# clocktal.net
KiCad netlist of a schematic drawn in EAGLE
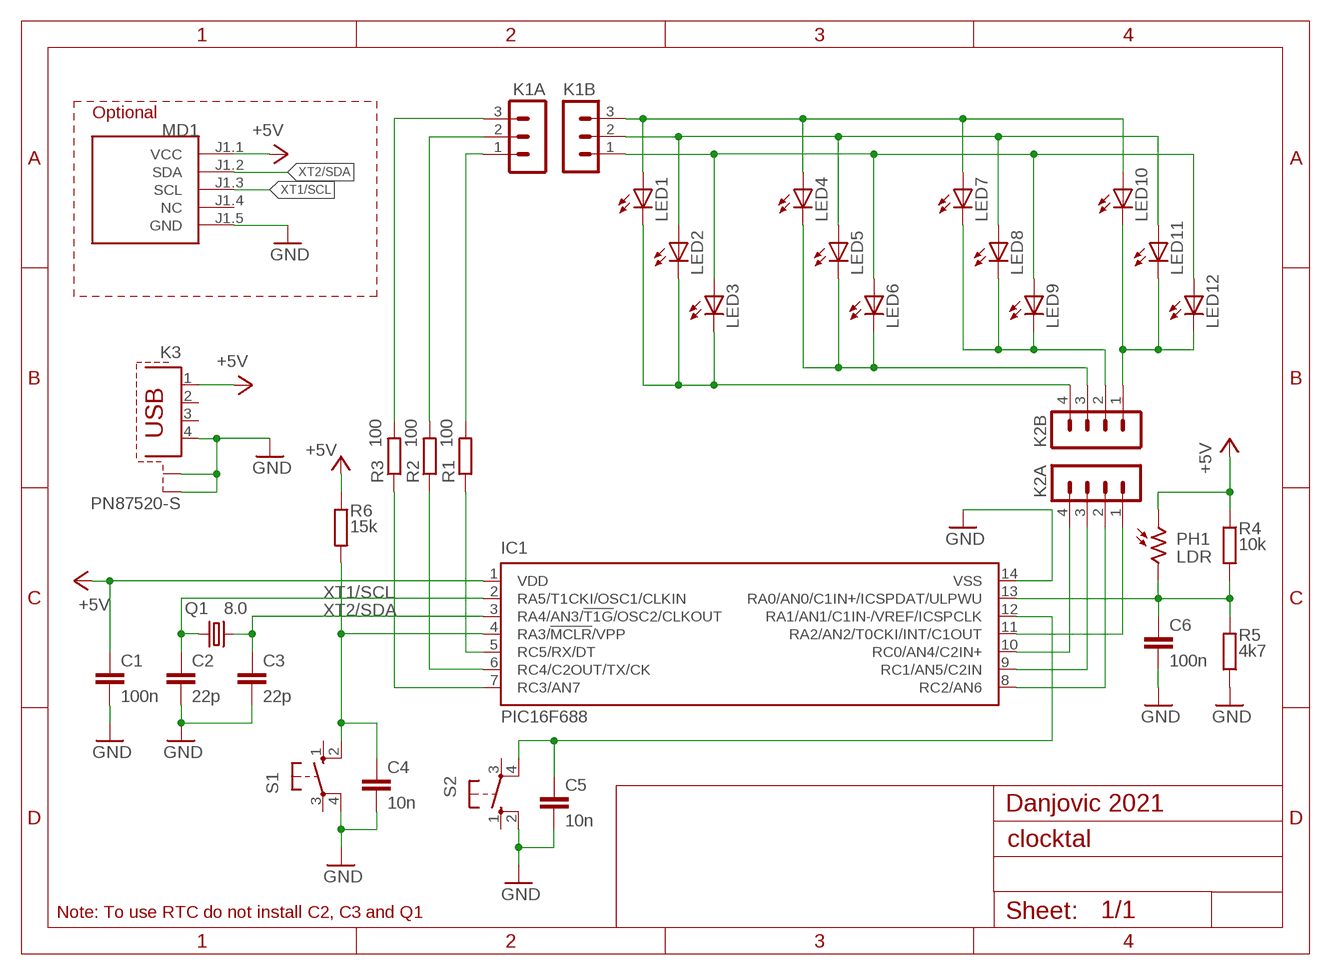
[diagram p0: schematic, sheet 1]

(export (version "E")
  (design (tool "Eeschema 10.0.6"))
  (components
    (comp (ref "C1")
      (value "100n")
      (footprint "eagle-import:C050-025X75L")
      (libsource (lib "eagle-import") (part "C-EUC050-025X075L"))
    )
    (comp (ref "C2")
      (value "22p")
      (footprint "eagle-import:C050-024X044L")
      (libsource (lib "eagle-import") (part "C-EUC050-024X044L"))
    )
    (comp (ref "C3")
      (value "22p")
      (footprint "eagle-import:C050-024X044L")
      (libsource (lib "eagle-import") (part "C-EUC050-024X044L"))
    )
    (comp (ref "C4")
      (value "10n")
      (footprint "eagle-import:C050-025X75L")
      (libsource (lib "eagle-import") (part "C-EUC050-025X075L"))
    )
    (comp (ref "C5")
      (value "10n")
      (footprint "eagle-import:C050-025X75L")
      (libsource (lib "eagle-import") (part "C-EUC050-025X075L"))
    )
    (comp (ref "C6")
      (value "100n")
      (footprint "eagle-import:C050-025X75L")
      (libsource (lib "eagle-import") (part "C-EUC050-025X075L"))
    )
    (comp (ref "IC1")
      (value "PIC16F688")
      (footprint "eagle-import:DIL14")
      (libsource (lib "eagle-import") (part "PIC16F688"))
    )
    (comp (ref "K1A")
      (value "MA03-1")
      (footprint "eagle-import:MA03-1")
      (libsource (lib "eagle-import") (part "MA03-1"))
    )
    (comp (ref "K1B")
      (value "MA03-1")
      (footprint "eagle-import:MA03-1")
      (libsource (lib "eagle-import") (part "MA03-1"))
    )
    (comp (ref "K2A")
      (value "MA04-1")
      (footprint "eagle-import:MA04-1")
      (libsource (lib "eagle-import") (part "MA04-1"))
    )
    (comp (ref "K2B")
      (value "MA04-1")
      (footprint "eagle-import:MA04-1")
      (libsource (lib "eagle-import") (part "MA04-1"))
    )
    (comp (ref "K3")
      (value "PN87520-S")
      (footprint "eagle-import:PN87520-S")
      (libsource (lib "eagle-import") (part "PN87520-S"))
    )
    (comp (ref "LED1")
      (value "LED3MM_L")
      (footprint "eagle-import:LED3MM_L")
      (libsource (lib "eagle-import") (part "LED3MM_L"))
    )
    (comp (ref "LED2")
      (value "LED3MM_L")
      (footprint "eagle-import:LED3MM_L")
      (libsource (lib "eagle-import") (part "LED3MM_L"))
    )
    (comp (ref "LED3")
      (value "LED3MM_L")
      (footprint "eagle-import:LED3MM_L")
      (libsource (lib "eagle-import") (part "LED3MM_L"))
    )
    (comp (ref "LED4")
      (value "LED3MM_L")
      (footprint "eagle-import:LED3MM_L")
      (libsource (lib "eagle-import") (part "LED3MM_L"))
    )
    (comp (ref "LED5")
      (value "LED3MM_L")
      (footprint "eagle-import:LED3MM_L")
      (libsource (lib "eagle-import") (part "LED3MM_L"))
    )
    (comp (ref "LED6")
      (value "LED3MM_L")
      (footprint "eagle-import:LED3MM_L")
      (libsource (lib "eagle-import") (part "LED3MM_L"))
    )
    (comp (ref "LED7")
      (value "LED3MM_L")
      (footprint "eagle-import:LED3MM_L")
      (libsource (lib "eagle-import") (part "LED3MM_L"))
    )
    (comp (ref "LED8")
      (value "LED3MM_L")
      (footprint "eagle-import:LED3MM_L")
      (libsource (lib "eagle-import") (part "LED3MM_L"))
    )
    (comp (ref "LED9")
      (value "LED3MM_L")
      (footprint "eagle-import:LED3MM_L")
      (libsource (lib "eagle-import") (part "LED3MM_L"))
    )
    (comp (ref "LED10")
      (value "LED3MM_L")
      (footprint "eagle-import:LED3MM_L")
      (libsource (lib "eagle-import") (part "LED3MM_L"))
    )
    (comp (ref "LED11")
      (value "LED3MM_L")
      (footprint "eagle-import:LED3MM_L")
      (libsource (lib "eagle-import") (part "LED3MM_L"))
    )
    (comp (ref "LED12")
      (value "LED3MM_L")
      (footprint "eagle-import:LED3MM_L")
      (libsource (lib "eagle-import") (part "LED3MM_L"))
    )
    (comp (ref "MD1")
      (value "RTC-DS3231_L")
      (footprint "eagle-import:RTC-DS3231-SMALL_L")
      (libsource (lib "eagle-import") (part "RTC-DS3231_L"))
    )
    (comp (ref "PH1")
      (value "LDR")
      (footprint "eagle-import:T0-46-A10XX")
      (libsource (lib "eagle-import") (part "A1050_09"))
    )
    (comp (ref "Q1")
      (value "8.0")
      (footprint "eagle-import:HC49U-V")
      (libsource (lib "eagle-import") (part "CRYSTALHC49U-V"))
    )
    (comp (ref "R1")
      (value "100")
      (footprint "eagle-import:0204_7L")
      (libsource (lib "eagle-import") (part "R-EU_0204/7L"))
    )
    (comp (ref "R2")
      (value "100")
      (footprint "eagle-import:0204_7L")
      (libsource (lib "eagle-import") (part "R-EU_0204/7L"))
    )
    (comp (ref "R3")
      (value "100")
      (footprint "eagle-import:0204_7L")
      (libsource (lib "eagle-import") (part "R-EU_0204/7L"))
    )
    (comp (ref "R4")
      (value "10k")
      (footprint "eagle-import:0204_7L")
      (libsource (lib "eagle-import") (part "R-EU_0204/7L"))
    )
    (comp (ref "R5")
      (value "4k7")
      (footprint "eagle-import:0204_7L")
      (libsource (lib "eagle-import") (part "R-EU_0204/7L"))
    )
    (comp (ref "R6")
      (value "15k")
      (footprint "eagle-import:0204_7L")
      (libsource (lib "eagle-import") (part "R-EU_0204/7L"))
    )
    (comp (ref "S1")
      (value "10-XX")
      (footprint "eagle-import:B3F-10XX")
      (fields (field (name "MPN") "B3F-1000"))
      (libsource (lib "eagle-import") (part "10-XX"))
    )
    (comp (ref "S2")
      (value "10-XX")
      (footprint "eagle-import:B3F-10XX")
      (fields (field (name "MPN") "B3F-1000"))
      (libsource (lib "eagle-import") (part "10-XX"))
    )
  )
  (nets
    (net (code "1") (name "+5V") (class "Default")
      (node (ref "C1") (pin "1") (pinfunction "1_1") (pintype "passive"))
      (node (ref "IC1") (pin "1") (pinfunction "VDD_1") (pintype "power_in"))
      (node (ref "K3") (pin "1") (pinfunction "1_1") (pintype "passive"))
      (node (ref "MD1") (pin "J1.1") (pinfunction "VCC_J1.1") (pintype "power_in"))
      (node (ref "PH1") (pin "1") (pinfunction "1_1") (pintype "passive"))
      (node (ref "R4") (pin "1") (pinfunction "1_1") (pintype "passive"))
      (node (ref "R6") (pin "1") (pinfunction "1_1") (pintype "passive"))
    )
    (net (code "2") (name "GND") (class "Default")
      (node (ref "C1") (pin "2") (pinfunction "2_2") (pintype "passive"))
      (node (ref "C2") (pin "2") (pinfunction "2_2") (pintype "passive"))
      (node (ref "C3") (pin "2") (pinfunction "2_2") (pintype "passive"))
      (node (ref "C4") (pin "2") (pinfunction "2_2") (pintype "passive"))
      (node (ref "C5") (pin "2") (pinfunction "2_2") (pintype "passive"))
      (node (ref "C6") (pin "2") (pinfunction "2_2") (pintype "passive"))
      (node (ref "IC1") (pin "14") (pinfunction "VSS_14") (pintype "power_in"))
      (node (ref "K3") (pin "4") (pinfunction "4_4") (pintype "passive"))
      (node (ref "K3") (pin "S1") (pinfunction "S1_S1") (pintype "passive"))
      (node (ref "K3") (pin "S2") (pinfunction "S2_S2") (pintype "passive"))
      (node (ref "MD1") (pin "J1.5") (pinfunction "GND_J1.5") (pintype "power_in"))
      (node (ref "R5") (pin "1") (pinfunction "1_1") (pintype "passive"))
      (node (ref "S1") (pin "4") (pinfunction "P1_4") (pintype "passive"))
      (node (ref "S2") (pin "2") (pinfunction "S1_2") (pintype "passive"))
    )
    (net (code "3") (name "Net-(IC1-RA0{slash}AN0{slash}C1IN+{slash}ICSPDAT{slash}ULPWU)") (class "Default")
      (node (ref "C6") (pin "1") (pinfunction "1_1") (pintype "passive"))
      (node (ref "IC1") (pin "13") (pinfunction "RA0/AN0/C1IN+/ICSPDAT/ULPWU_13") (pintype "bidirectional"))
      (node (ref "PH1") (pin "2") (pinfunction "2_2") (pintype "passive"))
      (node (ref "R4") (pin "2") (pinfunction "2_2") (pintype "passive"))
      (node (ref "R5") (pin "2") (pinfunction "2_2") (pintype "passive"))
    )
    (net (code "4") (name "Net-(IC1-RA1{slash}AN1{slash}C1IN-{slash}VREF{slash}ICSPCLK)") (class "Default")
      (node (ref "C5") (pin "1") (pinfunction "1_1") (pintype "passive"))
      (node (ref "IC1") (pin "12") (pinfunction "RA1/AN1/C1IN-/VREF/ICSPCLK_12") (pintype "bidirectional"))
      (node (ref "S2") (pin "4") (pinfunction "P1_4") (pintype "passive"))
    )
    (net (code "5") (name "Net-(IC1-RA2{slash}AN2{slash}T0CKI{slash}INT{slash}C1OUT)") (class "Default")
      (node (ref "IC1") (pin "11") (pinfunction "RA2/AN2/T0CKI/INT/C1OUT_11") (pintype "bidirectional"))
      (node (ref "K2A") (pin "1") (pinfunction "1_1") (pintype "passive"))
    )
    (net (code "6") (name "Net-(IC1-RA3{slash}~{MCLR}{slash}VPP)") (class "Default")
      (node (ref "C4") (pin "1") (pinfunction "1_1") (pintype "passive"))
      (node (ref "IC1") (pin "4") (pinfunction "RA3/~{MCLR}/VPP_4") (pintype "bidirectional"))
      (node (ref "R6") (pin "2") (pinfunction "2_2") (pintype "passive"))
      (node (ref "S1") (pin "2") (pinfunction "S1_2") (pintype "passive"))
    )
    (net (code "7") (name "Net-(IC1-RC0{slash}AN4{slash}C2IN+)") (class "Default")
      (node (ref "IC1") (pin "10") (pinfunction "RC0/AN4/C2IN+_10") (pintype "bidirectional"))
      (node (ref "K2A") (pin "4") (pinfunction "4_4") (pintype "passive"))
    )
    (net (code "8") (name "Net-(IC1-RC1{slash}AN5{slash}C2IN)") (class "Default")
      (node (ref "IC1") (pin "9") (pinfunction "RC1/AN5/C2IN_9") (pintype "bidirectional"))
      (node (ref "K2A") (pin "3") (pinfunction "3_3") (pintype "passive"))
    )
    (net (code "9") (name "Net-(IC1-RC2{slash}AN6)") (class "Default")
      (node (ref "IC1") (pin "8") (pinfunction "RC2/AN6_8") (pintype "bidirectional"))
      (node (ref "K2A") (pin "2") (pinfunction "2_2") (pintype "passive"))
    )
    (net (code "10") (name "Net-(IC1-RC3{slash}AN7)") (class "Default")
      (node (ref "IC1") (pin "7") (pinfunction "RC3/AN7_7") (pintype "bidirectional"))
      (node (ref "R3") (pin "1") (pinfunction "1_1") (pintype "passive"))
    )
    (net (code "11") (name "Net-(IC1-RC4{slash}C2OUT{slash}TX{slash}CK)") (class "Default")
      (node (ref "IC1") (pin "6") (pinfunction "RC4/C2OUT/TX/CK_6") (pintype "bidirectional"))
      (node (ref "R2") (pin "1") (pinfunction "1_1") (pintype "passive"))
    )
    (net (code "12") (name "Net-(IC1-RC5{slash}RX{slash}DT)") (class "Default")
      (node (ref "IC1") (pin "5") (pinfunction "RC5/RX/DT_5") (pintype "bidirectional"))
      (node (ref "R1") (pin "1") (pinfunction "1_1") (pintype "passive"))
    )
    (net (code "13") (name "Net-(K1A-Pad1)") (class "Default")
      (node (ref "K1A") (pin "1") (pinfunction "1_1") (pintype "passive"))
      (node (ref "R1") (pin "2") (pinfunction "2_2") (pintype "passive"))
    )
    (net (code "14") (name "Net-(K1A-Pad2)") (class "Default")
      (node (ref "K1A") (pin "2") (pinfunction "2_2") (pintype "passive"))
      (node (ref "R2") (pin "2") (pinfunction "2_2") (pintype "passive"))
    )
    (net (code "15") (name "Net-(K1A-Pad3)") (class "Default")
      (node (ref "K1A") (pin "3") (pinfunction "3_3") (pintype "passive"))
      (node (ref "R3") (pin "2") (pinfunction "2_2") (pintype "passive"))
    )
    (net (code "16") (name "Net-(K1B-Pad1)") (class "Default")
      (node (ref "K1B") (pin "1") (pinfunction "1_1") (pintype "passive"))
      (node (ref "LED12") (pin "A") (pinfunction "A_A") (pintype "passive"))
      (node (ref "LED3") (pin "A") (pinfunction "A_A") (pintype "passive"))
      (node (ref "LED6") (pin "A") (pinfunction "A_A") (pintype "passive"))
      (node (ref "LED9") (pin "A") (pinfunction "A_A") (pintype "passive"))
    )
    (net (code "17") (name "Net-(K1B-Pad2)") (class "Default")
      (node (ref "K1B") (pin "2") (pinfunction "2_2") (pintype "passive"))
      (node (ref "LED11") (pin "A") (pinfunction "A_A") (pintype "passive"))
      (node (ref "LED2") (pin "A") (pinfunction "A_A") (pintype "passive"))
      (node (ref "LED5") (pin "A") (pinfunction "A_A") (pintype "passive"))
      (node (ref "LED8") (pin "A") (pinfunction "A_A") (pintype "passive"))
    )
    (net (code "18") (name "Net-(K1B-Pad3)") (class "Default")
      (node (ref "K1B") (pin "3") (pinfunction "3_3") (pintype "passive"))
      (node (ref "LED1") (pin "A") (pinfunction "A_A") (pintype "passive"))
      (node (ref "LED10") (pin "A") (pinfunction "A_A") (pintype "passive"))
      (node (ref "LED4") (pin "A") (pinfunction "A_A") (pintype "passive"))
      (node (ref "LED7") (pin "A") (pinfunction "A_A") (pintype "passive"))
    )
    (net (code "19") (name "Net-(LED1-C)") (class "Default")
      (node (ref "K2B") (pin "4") (pinfunction "4_4") (pintype "passive"))
      (node (ref "LED1") (pin "K") (pinfunction "C_K") (pintype "passive"))
      (node (ref "LED2") (pin "K") (pinfunction "C_K") (pintype "passive"))
      (node (ref "LED3") (pin "K") (pinfunction "C_K") (pintype "passive"))
    )
    (net (code "20") (name "Net-(LED4-C)") (class "Default")
      (node (ref "K2B") (pin "3") (pinfunction "3_3") (pintype "passive"))
      (node (ref "LED4") (pin "K") (pinfunction "C_K") (pintype "passive"))
      (node (ref "LED5") (pin "K") (pinfunction "C_K") (pintype "passive"))
      (node (ref "LED6") (pin "K") (pinfunction "C_K") (pintype "passive"))
    )
    (net (code "21") (name "Net-(LED7-C)") (class "Default")
      (node (ref "K2B") (pin "2") (pinfunction "2_2") (pintype "passive"))
      (node (ref "LED7") (pin "K") (pinfunction "C_K") (pintype "passive"))
      (node (ref "LED8") (pin "K") (pinfunction "C_K") (pintype "passive"))
      (node (ref "LED9") (pin "K") (pinfunction "C_K") (pintype "passive"))
    )
    (net (code "22") (name "Net-(LED10-C)") (class "Default")
      (node (ref "K2B") (pin "1") (pinfunction "1_1") (pintype "passive"))
      (node (ref "LED10") (pin "K") (pinfunction "C_K") (pintype "passive"))
      (node (ref "LED11") (pin "K") (pinfunction "C_K") (pintype "passive"))
      (node (ref "LED12") (pin "K") (pinfunction "C_K") (pintype "passive"))
    )
    (net (code "23") (name "XT1{slash}SCL") (class "Default")
      (node (ref "C2") (pin "1") (pinfunction "1_1") (pintype "passive"))
      (node (ref "IC1") (pin "2") (pinfunction "RA5/T1CKI/OSC1/CLKIN_2") (pintype "input"))
      (node (ref "MD1") (pin "J1.3") (pinfunction "SCL_J1.3") (pintype "bidirectional"))
      (node (ref "Q1") (pin "1") (pinfunction "1_1") (pintype "passive"))
    )
    (net (code "24") (name "XT2{slash}SDA") (class "Default")
      (node (ref "C3") (pin "1") (pinfunction "1_1") (pintype "passive"))
      (node (ref "IC1") (pin "3") (pinfunction "RA4/AN3/~{T1G}/OSC2/CLKOUT_3") (pintype "bidirectional"))
      (node (ref "MD1") (pin "J1.2") (pinfunction "SDA_J1.2") (pintype "bidirectional"))
      (node (ref "Q1") (pin "2") (pinfunction "2_2") (pintype "passive"))
    )
    (net (code "25") (name "unconnected-(K3-Pad2)") (class "Default")
      (node (ref "K3") (pin "2") (pinfunction "2_2") (pintype "passive"))
    )
    (net (code "26") (name "unconnected-(K3-Pad3)") (class "Default")
      (node (ref "K3") (pin "3") (pinfunction "3_3") (pintype "passive"))
    )
    (net (code "27") (name "unconnected-(MD1-NC-PadJ1.4)") (class "Default")
      (node (ref "MD1") (pin "J1.4") (pinfunction "NC_J1.4") (pintype "bidirectional"))
    )
    (net (code "28") (name "unconnected-(S1-P-Pad3)") (class "Default")
      (node (ref "S1") (pin "3") (pinfunction "P_3") (pintype "passive"))
    )
    (net (code "29") (name "unconnected-(S1-S-Pad1)") (class "Default")
      (node (ref "S1") (pin "1") (pinfunction "S_1") (pintype "passive"))
    )
    (net (code "30") (name "unconnected-(S2-P-Pad3)") (class "Default")
      (node (ref "S2") (pin "3") (pinfunction "P_3") (pintype "passive"))
    )
    (net (code "31") (name "unconnected-(S2-S-Pad1)") (class "Default")
      (node (ref "S2") (pin "1") (pinfunction "S_1") (pintype "passive"))
    )
  )
)
